# Drivers_V2.net
KiCad netlist of a schematic drawn in Altium Designer
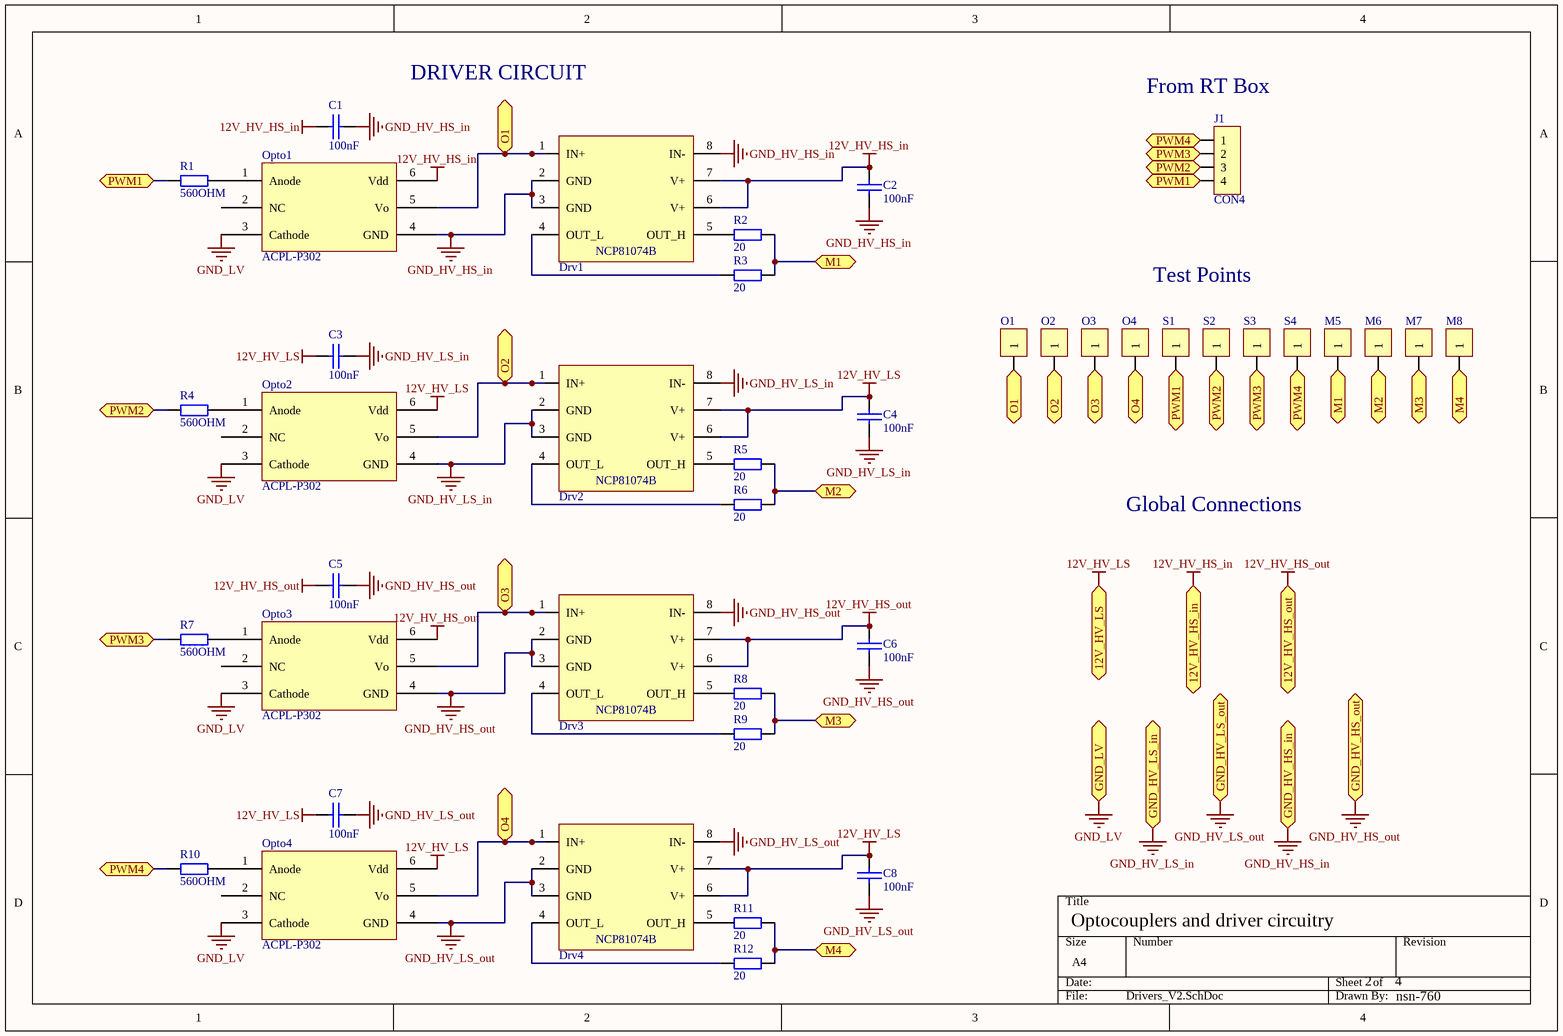
[diagram p0: Drivers_V2.SchDoc]

(export (version "E")
  (design (tool "Eeschema 10.0.6"))
  (components
    (comp (ref "C1")
      (value "100nF")
      (footprint "1206")
      (description "Condensador")
      (libsource (lib "SCH_Lib") (part "Condensador"))
    )
    (comp (ref "C2")
      (value "100nF")
      (footprint "1206")
      (description "Condensador")
      (libsource (lib "SCH_Lib") (part "Condensador"))
    )
    (comp (ref "C3")
      (value "100nF")
      (footprint "1206")
      (description "Condensador")
      (libsource (lib "SCH_Lib") (part "Condensador"))
    )
    (comp (ref "C4")
      (value "100nF")
      (footprint "1206")
      (description "Condensador")
      (libsource (lib "SCH_Lib") (part "Condensador"))
    )
    (comp (ref "C5")
      (value "100nF")
      (footprint "1206")
      (description "Condensador")
      (libsource (lib "SCH_Lib") (part "Condensador"))
    )
    (comp (ref "C6")
      (value "100nF")
      (footprint "1206")
      (description "Condensador")
      (libsource (lib "SCH_Lib") (part "Condensador"))
    )
    (comp (ref "C7")
      (value "100nF")
      (footprint "1206")
      (description "Condensador")
      (libsource (lib "SCH_Lib") (part "Condensador"))
    )
    (comp (ref "C8")
      (value "100nF")
      (footprint "1206")
      (description "Condensador")
      (libsource (lib "SCH_Lib") (part "Condensador"))
    )
    (comp (ref "Drv1")
      (value "NCP81074B")
      (footprint "NCP81074A")
      (libsource (lib "SCH_Lib") (part "NCP81074B"))
    )
    (comp (ref "Drv2")
      (value "NCP81074B")
      (footprint "NCP81074A")
      (libsource (lib "SCH_Lib") (part "NCP81074B"))
    )
    (comp (ref "Drv3")
      (value "NCP81074B")
      (footprint "NCP81074A")
      (libsource (lib "SCH_Lib") (part "NCP81074B"))
    )
    (comp (ref "Drv4")
      (value "NCP81074B")
      (footprint "NCP81074A")
      (libsource (lib "SCH_Lib") (part "NCP81074B"))
    )
    (comp (ref "J1")
      (value "CON4")
      (footprint "Con4_Extron _3.5mmPitch")
      (libsource (lib "SCH_Lib") (part "CON4"))
    )
    (comp (ref "M5")
      (value "Test Point")
      (footprint "Test_Point")
      (libsource (lib "SCH_Lib") (part "Test Point"))
    )
    (comp (ref "M6")
      (value "Test Point")
      (footprint "Test_Point")
      (libsource (lib "SCH_Lib") (part "Test Point"))
    )
    (comp (ref "M7")
      (value "Test Point")
      (footprint "Test_Point")
      (libsource (lib "SCH_Lib") (part "Test Point"))
    )
    (comp (ref "M8")
      (value "Test Point")
      (footprint "Test_Point")
      (libsource (lib "SCH_Lib") (part "Test Point"))
    )
    (comp (ref "O1")
      (value "Test Point")
      (footprint "Test_Point")
      (libsource (lib "SCH_Lib") (part "Test Point"))
    )
    (comp (ref "O2")
      (value "Test Point")
      (footprint "Test_Point")
      (libsource (lib "SCH_Lib") (part "Test Point"))
    )
    (comp (ref "O3")
      (value "Test Point")
      (footprint "Test_Point")
      (libsource (lib "SCH_Lib") (part "Test Point"))
    )
    (comp (ref "O4")
      (value "Test Point")
      (footprint "Test_Point")
      (libsource (lib "SCH_Lib") (part "Test Point"))
    )
    (comp (ref "Opto1")
      (value "ACPL-P302")
      (footprint "SSOIC6")
      (libsource (lib "SCH_Lib") (part "Opto_ACPL"))
    )
    (comp (ref "Opto2")
      (value "ACPL-P302")
      (footprint "SSOIC6")
      (libsource (lib "SCH_Lib") (part "Opto_ACPL"))
    )
    (comp (ref "Opto3")
      (value "ACPL-P302")
      (footprint "SSOIC6")
      (libsource (lib "SCH_Lib") (part "Opto_ACPL"))
    )
    (comp (ref "Opto4")
      (value "ACPL-P302")
      (footprint "SSOIC6")
      (libsource (lib "SCH_Lib") (part "Opto_ACPL"))
    )
    (comp (ref "R1")
      (value "560OHM")
      (footprint "1206")
      (description "Resistencia")
      (libsource (lib "SCH_Lib") (part "Resistencia"))
    )
    (comp (ref "R2")
      (value "20")
      (footprint "1206")
      (description "Resistencia")
      (libsource (lib "SCH_Lib") (part "Resistencia"))
    )
    (comp (ref "R3")
      (value "20")
      (footprint "1206")
      (description "Resistencia")
      (libsource (lib "SCH_Lib") (part "Resistencia"))
    )
    (comp (ref "R4")
      (value "560OHM")
      (footprint "1206")
      (description "Resistencia")
      (libsource (lib "SCH_Lib") (part "Resistencia"))
    )
    (comp (ref "R5")
      (value "20")
      (footprint "1206")
      (description "Resistencia")
      (libsource (lib "SCH_Lib") (part "Resistencia"))
    )
    (comp (ref "R6")
      (value "20")
      (footprint "1206")
      (description "Resistencia")
      (libsource (lib "SCH_Lib") (part "Resistencia"))
    )
    (comp (ref "R7")
      (value "560OHM")
      (footprint "1206")
      (description "Resistencia")
      (libsource (lib "SCH_Lib") (part "Resistencia"))
    )
    (comp (ref "R8")
      (value "20")
      (footprint "1206")
      (description "Resistencia")
      (libsource (lib "SCH_Lib") (part "Resistencia"))
    )
    (comp (ref "R9")
      (value "20")
      (footprint "1206")
      (description "Resistencia")
      (libsource (lib "SCH_Lib") (part "Resistencia"))
    )
    (comp (ref "R10")
      (value "560OHM")
      (footprint "1206")
      (description "Resistencia")
      (libsource (lib "SCH_Lib") (part "Resistencia"))
    )
    (comp (ref "R11")
      (value "20")
      (footprint "1206")
      (description "Resistencia")
      (libsource (lib "SCH_Lib") (part "Resistencia"))
    )
    (comp (ref "R12")
      (value "20")
      (footprint "1206")
      (description "Resistencia")
      (libsource (lib "SCH_Lib") (part "Resistencia"))
    )
    (comp (ref "S1")
      (value "Test Point")
      (footprint "Test_Point")
      (libsource (lib "SCH_Lib") (part "Test Point"))
    )
    (comp (ref "S2")
      (value "Test Point")
      (footprint "Test_Point")
      (libsource (lib "SCH_Lib") (part "Test Point"))
    )
    (comp (ref "S3")
      (value "Test Point")
      (footprint "Test_Point")
      (libsource (lib "SCH_Lib") (part "Test Point"))
    )
    (comp (ref "S4")
      (value "Test Point")
      (footprint "Test_Point")
      (libsource (lib "SCH_Lib") (part "Test Point"))
    )
  )
  (nets
    (net (code "1") (name "/M1") (class "Default")
      (node (ref "M5") (pin "1") (pinfunction "1_1") (pintype "passive"))
      (node (ref "R2") (pin "1") (pinfunction "1_1") (pintype "passive"))
      (node (ref "R3") (pin "1") (pinfunction "1_1") (pintype "passive"))
    )
    (net (code "2") (name "/M2") (class "Default")
      (node (ref "M6") (pin "1") (pinfunction "1_1") (pintype "passive"))
      (node (ref "R5") (pin "1") (pinfunction "1_1") (pintype "passive"))
      (node (ref "R6") (pin "1") (pinfunction "1_1") (pintype "passive"))
    )
    (net (code "3") (name "/M3") (class "Default")
      (node (ref "M7") (pin "1") (pinfunction "1_1") (pintype "passive"))
      (node (ref "R8") (pin "1") (pinfunction "1_1") (pintype "passive"))
      (node (ref "R9") (pin "1") (pinfunction "1_1") (pintype "passive"))
    )
    (net (code "4") (name "/M4") (class "Default")
      (node (ref "M8") (pin "1") (pinfunction "1_1") (pintype "passive"))
      (node (ref "R11") (pin "1") (pinfunction "1_1") (pintype "passive"))
      (node (ref "R12") (pin "1") (pinfunction "1_1") (pintype "passive"))
    )
    (net (code "5") (name "/O1") (class "Default")
      (node (ref "Drv1") (pin "1") (pinfunction "IN+_1") (pintype "passive"))
      (node (ref "O1") (pin "1") (pinfunction "1_1") (pintype "passive"))
      (node (ref "Opto1") (pin "5") (pinfunction "Vo_5") (pintype "passive"))
    )
    (net (code "6") (name "/O2") (class "Default")
      (node (ref "Drv2") (pin "1") (pinfunction "IN+_1") (pintype "passive"))
      (node (ref "O2") (pin "1") (pinfunction "1_1") (pintype "passive"))
      (node (ref "Opto2") (pin "5") (pinfunction "Vo_5") (pintype "passive"))
    )
    (net (code "7") (name "/O3") (class "Default")
      (node (ref "Drv3") (pin "1") (pinfunction "IN+_1") (pintype "passive"))
      (node (ref "O3") (pin "1") (pinfunction "1_1") (pintype "passive"))
      (node (ref "Opto3") (pin "5") (pinfunction "Vo_5") (pintype "passive"))
    )
    (net (code "8") (name "/O4") (class "Default")
      (node (ref "Drv4") (pin "1") (pinfunction "IN+_1") (pintype "passive"))
      (node (ref "O4") (pin "1") (pinfunction "1_1") (pintype "passive"))
      (node (ref "Opto4") (pin "5") (pinfunction "Vo_5") (pintype "passive"))
    )
    (net (code "9") (name "/PWM1") (class "Default")
      (node (ref "J1") (pin "4") (pinfunction "4_4") (pintype "passive"))
      (node (ref "R1") (pin "2") (pinfunction "2_2") (pintype "passive"))
      (node (ref "S1") (pin "1") (pinfunction "1_1") (pintype "passive"))
    )
    (net (code "10") (name "/PWM2") (class "Default")
      (node (ref "J1") (pin "3") (pinfunction "3_3") (pintype "passive"))
      (node (ref "R4") (pin "2") (pinfunction "2_2") (pintype "passive"))
      (node (ref "S2") (pin "1") (pinfunction "1_1") (pintype "passive"))
    )
    (net (code "11") (name "/PWM3") (class "Default")
      (node (ref "J1") (pin "2") (pinfunction "2_2") (pintype "passive"))
      (node (ref "R7") (pin "2") (pinfunction "2_2") (pintype "passive"))
      (node (ref "S3") (pin "1") (pinfunction "1_1") (pintype "passive"))
    )
    (net (code "12") (name "/PWM4") (class "Default")
      (node (ref "J1") (pin "1") (pinfunction "1_1") (pintype "passive"))
      (node (ref "R10") (pin "2") (pinfunction "2_2") (pintype "passive"))
      (node (ref "S4") (pin "1") (pinfunction "1_1") (pintype "passive"))
    )
    (net (code "13") (name "12V_HV_HS_in") (class "Default")
      (node (ref "C1") (pin "1") (pintype "passive"))
      (node (ref "C2") (pin "1") (pintype "passive"))
      (node (ref "Drv1") (pin "6") (pinfunction "V+_6") (pintype "passive"))
      (node (ref "Drv1") (pin "7") (pinfunction "V+_7") (pintype "passive"))
      (node (ref "Opto1") (pin "6") (pinfunction "Vdd_6") (pintype "passive"))
    )
    (net (code "14") (name "12V_HV_HS_out") (class "Default")
      (node (ref "C5") (pin "1") (pintype "passive"))
      (node (ref "C6") (pin "1") (pintype "passive"))
      (node (ref "Drv3") (pin "6") (pinfunction "V+_6") (pintype "passive"))
      (node (ref "Drv3") (pin "7") (pinfunction "V+_7") (pintype "passive"))
      (node (ref "Opto3") (pin "6") (pinfunction "Vdd_6") (pintype "passive"))
    )
    (net (code "15") (name "12V_HV_LS") (class "Default")
      (node (ref "C3") (pin "1") (pintype "passive"))
      (node (ref "C4") (pin "1") (pintype "passive"))
      (node (ref "C7") (pin "1") (pintype "passive"))
      (node (ref "C8") (pin "1") (pintype "passive"))
      (node (ref "Drv2") (pin "6") (pinfunction "V+_6") (pintype "passive"))
      (node (ref "Drv2") (pin "7") (pinfunction "V+_7") (pintype "passive"))
      (node (ref "Drv4") (pin "6") (pinfunction "V+_6") (pintype "passive"))
      (node (ref "Drv4") (pin "7") (pinfunction "V+_7") (pintype "passive"))
      (node (ref "Opto2") (pin "6") (pinfunction "Vdd_6") (pintype "passive"))
      (node (ref "Opto4") (pin "6") (pinfunction "Vdd_6") (pintype "passive"))
    )
    (net (code "16") (name "GND_HV_HS_in") (class "Default")
      (node (ref "C1") (pin "2") (pintype "passive"))
      (node (ref "C2") (pin "2") (pintype "passive"))
      (node (ref "Drv1") (pin "2") (pinfunction "GND_2") (pintype "passive"))
      (node (ref "Drv1") (pin "3") (pinfunction "GND_3") (pintype "passive"))
      (node (ref "Drv1") (pin "8") (pinfunction "IN-_8") (pintype "passive"))
      (node (ref "Opto1") (pin "4") (pinfunction "GND_4") (pintype "passive"))
    )
    (net (code "17") (name "GND_HV_HS_out") (class "Default")
      (node (ref "C5") (pin "2") (pintype "passive"))
      (node (ref "C6") (pin "2") (pintype "passive"))
      (node (ref "Drv3") (pin "2") (pinfunction "GND_2") (pintype "passive"))
      (node (ref "Drv3") (pin "3") (pinfunction "GND_3") (pintype "passive"))
      (node (ref "Drv3") (pin "8") (pinfunction "IN-_8") (pintype "passive"))
      (node (ref "Opto3") (pin "4") (pinfunction "GND_4") (pintype "passive"))
    )
    (net (code "18") (name "GND_HV_LS_in") (class "Default")
      (node (ref "C3") (pin "2") (pintype "passive"))
      (node (ref "C4") (pin "2") (pintype "passive"))
      (node (ref "Drv2") (pin "2") (pinfunction "GND_2") (pintype "passive"))
      (node (ref "Drv2") (pin "3") (pinfunction "GND_3") (pintype "passive"))
      (node (ref "Drv2") (pin "8") (pinfunction "IN-_8") (pintype "passive"))
      (node (ref "Opto2") (pin "4") (pinfunction "GND_4") (pintype "passive"))
    )
    (net (code "19") (name "GND_HV_LS_out") (class "Default")
      (node (ref "C7") (pin "2") (pintype "passive"))
      (node (ref "C8") (pin "2") (pintype "passive"))
      (node (ref "Drv4") (pin "2") (pinfunction "GND_2") (pintype "passive"))
      (node (ref "Drv4") (pin "3") (pinfunction "GND_3") (pintype "passive"))
      (node (ref "Drv4") (pin "8") (pinfunction "IN-_8") (pintype "passive"))
      (node (ref "Opto4") (pin "4") (pinfunction "GND_4") (pintype "passive"))
    )
    (net (code "20") (name "GND_LV") (class "Default")
      (node (ref "Opto1") (pin "3") (pinfunction "Cathode_3") (pintype "passive"))
      (node (ref "Opto2") (pin "3") (pinfunction "Cathode_3") (pintype "passive"))
      (node (ref "Opto3") (pin "3") (pinfunction "Cathode_3") (pintype "passive"))
      (node (ref "Opto4") (pin "3") (pinfunction "Cathode_3") (pintype "passive"))
    )
    (net (code "21") (name "Net-(Drv1-OUT_H)") (class "Default")
      (node (ref "Drv1") (pin "5") (pinfunction "OUT_H_5") (pintype "passive"))
      (node (ref "R2") (pin "2") (pinfunction "2_2") (pintype "passive"))
    )
    (net (code "22") (name "Net-(Drv1-OUT_L)") (class "Default")
      (node (ref "Drv1") (pin "4") (pinfunction "OUT_L_4") (pintype "passive"))
      (node (ref "R3") (pin "2") (pinfunction "2_2") (pintype "passive"))
    )
    (net (code "23") (name "Net-(Drv2-OUT_H)") (class "Default")
      (node (ref "Drv2") (pin "5") (pinfunction "OUT_H_5") (pintype "passive"))
      (node (ref "R5") (pin "2") (pinfunction "2_2") (pintype "passive"))
    )
    (net (code "24") (name "Net-(Drv2-OUT_L)") (class "Default")
      (node (ref "Drv2") (pin "4") (pinfunction "OUT_L_4") (pintype "passive"))
      (node (ref "R6") (pin "2") (pinfunction "2_2") (pintype "passive"))
    )
    (net (code "25") (name "Net-(Drv3-OUT_H)") (class "Default")
      (node (ref "Drv3") (pin "5") (pinfunction "OUT_H_5") (pintype "passive"))
      (node (ref "R8") (pin "2") (pinfunction "2_2") (pintype "passive"))
    )
    (net (code "26") (name "Net-(Drv3-OUT_L)") (class "Default")
      (node (ref "Drv3") (pin "4") (pinfunction "OUT_L_4") (pintype "passive"))
      (node (ref "R9") (pin "2") (pinfunction "2_2") (pintype "passive"))
    )
    (net (code "27") (name "Net-(Drv4-OUT_H)") (class "Default")
      (node (ref "Drv4") (pin "5") (pinfunction "OUT_H_5") (pintype "passive"))
      (node (ref "R11") (pin "2") (pinfunction "2_2") (pintype "passive"))
    )
    (net (code "28") (name "Net-(Drv4-OUT_L)") (class "Default")
      (node (ref "Drv4") (pin "4") (pinfunction "OUT_L_4") (pintype "passive"))
      (node (ref "R12") (pin "2") (pinfunction "2_2") (pintype "passive"))
    )
    (net (code "29") (name "Net-(Opto1-Anode)") (class "Default")
      (node (ref "Opto1") (pin "1") (pinfunction "Anode_1") (pintype "passive"))
      (node (ref "R1") (pin "1") (pinfunction "1_1") (pintype "passive"))
    )
    (net (code "30") (name "Net-(Opto2-Anode)") (class "Default")
      (node (ref "Opto2") (pin "1") (pinfunction "Anode_1") (pintype "passive"))
      (node (ref "R4") (pin "1") (pinfunction "1_1") (pintype "passive"))
    )
    (net (code "31") (name "Net-(Opto3-Anode)") (class "Default")
      (node (ref "Opto3") (pin "1") (pinfunction "Anode_1") (pintype "passive"))
      (node (ref "R7") (pin "1") (pinfunction "1_1") (pintype "passive"))
    )
    (net (code "32") (name "Net-(Opto4-Anode)") (class "Default")
      (node (ref "Opto4") (pin "1") (pinfunction "Anode_1") (pintype "passive"))
      (node (ref "R10") (pin "1") (pinfunction "1_1") (pintype "passive"))
    )
    (net (code "33") (name "unconnected-(Opto1-NC-Pad2)") (class "Default")
      (node (ref "Opto1") (pin "2") (pinfunction "NC_2") (pintype "passive"))
    )
    (net (code "34") (name "unconnected-(Opto2-NC-Pad2)") (class "Default")
      (node (ref "Opto2") (pin "2") (pinfunction "NC_2") (pintype "passive"))
    )
    (net (code "35") (name "unconnected-(Opto3-NC-Pad2)") (class "Default")
      (node (ref "Opto3") (pin "2") (pinfunction "NC_2") (pintype "passive"))
    )
    (net (code "36") (name "unconnected-(Opto4-NC-Pad2)") (class "Default")
      (node (ref "Opto4") (pin "2") (pinfunction "NC_2") (pintype "passive"))
    )
  )
)
